# OutputConnection.net
KiCad netlist of a schematic drawn in Altium Designer
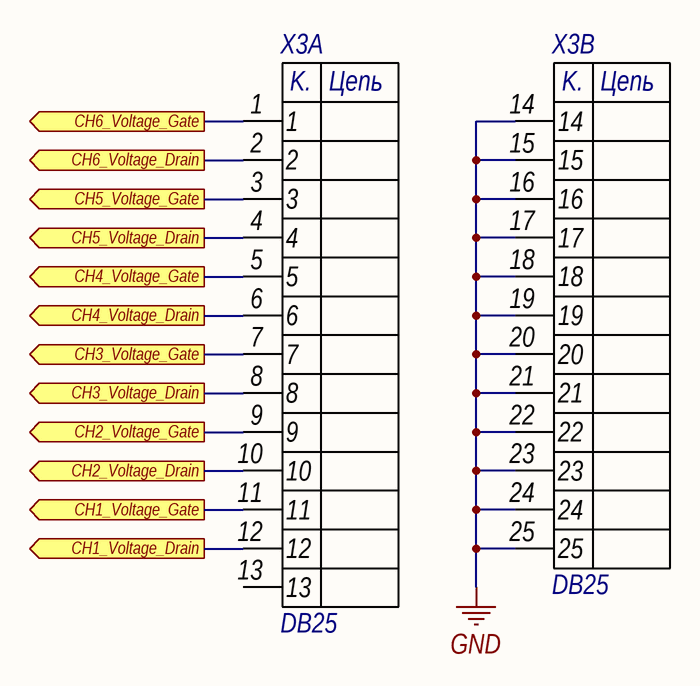
[diagram p0: OutputConnection.SchDoc]

(export (version "E")
  (design (tool "Eeschema 10.0.6"))
  (components (comp (ref "X3") (value "DB25") (footprint "DB25F") (libsource (lib "ComLib") (part "DB25"))))
  (nets
    (net (code "1") (name "/CH1_Voltage_Drain") (class "Default")
      (node (ref "X3") (pin "12") (pinfunction "12_12") (pintype "passive"))
    )
    (net (code "2") (name "/CH1_Voltage_Gate") (class "Default")
      (node (ref "X3") (pin "11") (pinfunction "11_11") (pintype "passive"))
    )
    (net (code "3") (name "/CH2_Voltage_Drain") (class "Default")
      (node (ref "X3") (pin "10") (pinfunction "10_10") (pintype "passive"))
    )
    (net (code "4") (name "/CH2_Voltage_Gate") (class "Default")
      (node (ref "X3") (pin "9") (pinfunction "9_9") (pintype "passive"))
    )
    (net (code "5") (name "/CH3_Voltage_Drain") (class "Default")
      (node (ref "X3") (pin "8") (pinfunction "8_8") (pintype "passive"))
    )
    (net (code "6") (name "/CH3_Voltage_Gate") (class "Default")
      (node (ref "X3") (pin "7") (pinfunction "7_7") (pintype "passive"))
    )
    (net (code "7") (name "/CH4_Voltage_Drain") (class "Default")
      (node (ref "X3") (pin "6") (pinfunction "6_6") (pintype "passive"))
    )
    (net (code "8") (name "/CH4_Voltage_Gate") (class "Default")
      (node (ref "X3") (pin "5") (pinfunction "5_5") (pintype "passive"))
    )
    (net (code "9") (name "/CH5_Voltage_Drain") (class "Default")
      (node (ref "X3") (pin "4") (pinfunction "4_4") (pintype "passive"))
    )
    (net (code "10") (name "/CH5_Voltage_Gate") (class "Default")
      (node (ref "X3") (pin "3") (pinfunction "3_3") (pintype "passive"))
    )
    (net (code "11") (name "/CH6_Voltage_Drain") (class "Default")
      (node (ref "X3") (pin "2") (pinfunction "2_2") (pintype "passive"))
    )
    (net (code "12") (name "/CH6_Voltage_Gate") (class "Default")
      (node (ref "X3") (pin "1") (pinfunction "1_1") (pintype "passive"))
    )
    (net (code "13") (name "GND") (class "Default")
      (node (ref "X3") (pin "14") (pinfunction "14_14") (pintype "passive"))
      (node (ref "X3") (pin "15") (pinfunction "15_15") (pintype "passive"))
      (node (ref "X3") (pin "16") (pinfunction "16_16") (pintype "passive"))
      (node (ref "X3") (pin "17") (pinfunction "17_17") (pintype "passive"))
      (node (ref "X3") (pin "18") (pinfunction "18_18") (pintype "passive"))
      (node (ref "X3") (pin "19") (pinfunction "19_19") (pintype "passive"))
      (node (ref "X3") (pin "20") (pinfunction "20_20") (pintype "passive"))
      (node (ref "X3") (pin "21") (pinfunction "21_21") (pintype "passive"))
      (node (ref "X3") (pin "22") (pinfunction "22_22") (pintype "passive"))
      (node (ref "X3") (pin "23") (pinfunction "23_23") (pintype "passive"))
      (node (ref "X3") (pin "24") (pinfunction "24_24") (pintype "passive"))
      (node (ref "X3") (pin "25") (pinfunction "25_25") (pintype "passive"))
    )
    (net (code "14") (name "unconnected-(X3-Pad13)") (class "Default")
      (node (ref "X3") (pin "13") (pinfunction "13_13") (pintype "passive"))
    )
  )
)
